# ETHERNET_PHY0.net
KiCad netlist of a schematic drawn in Altium Designer
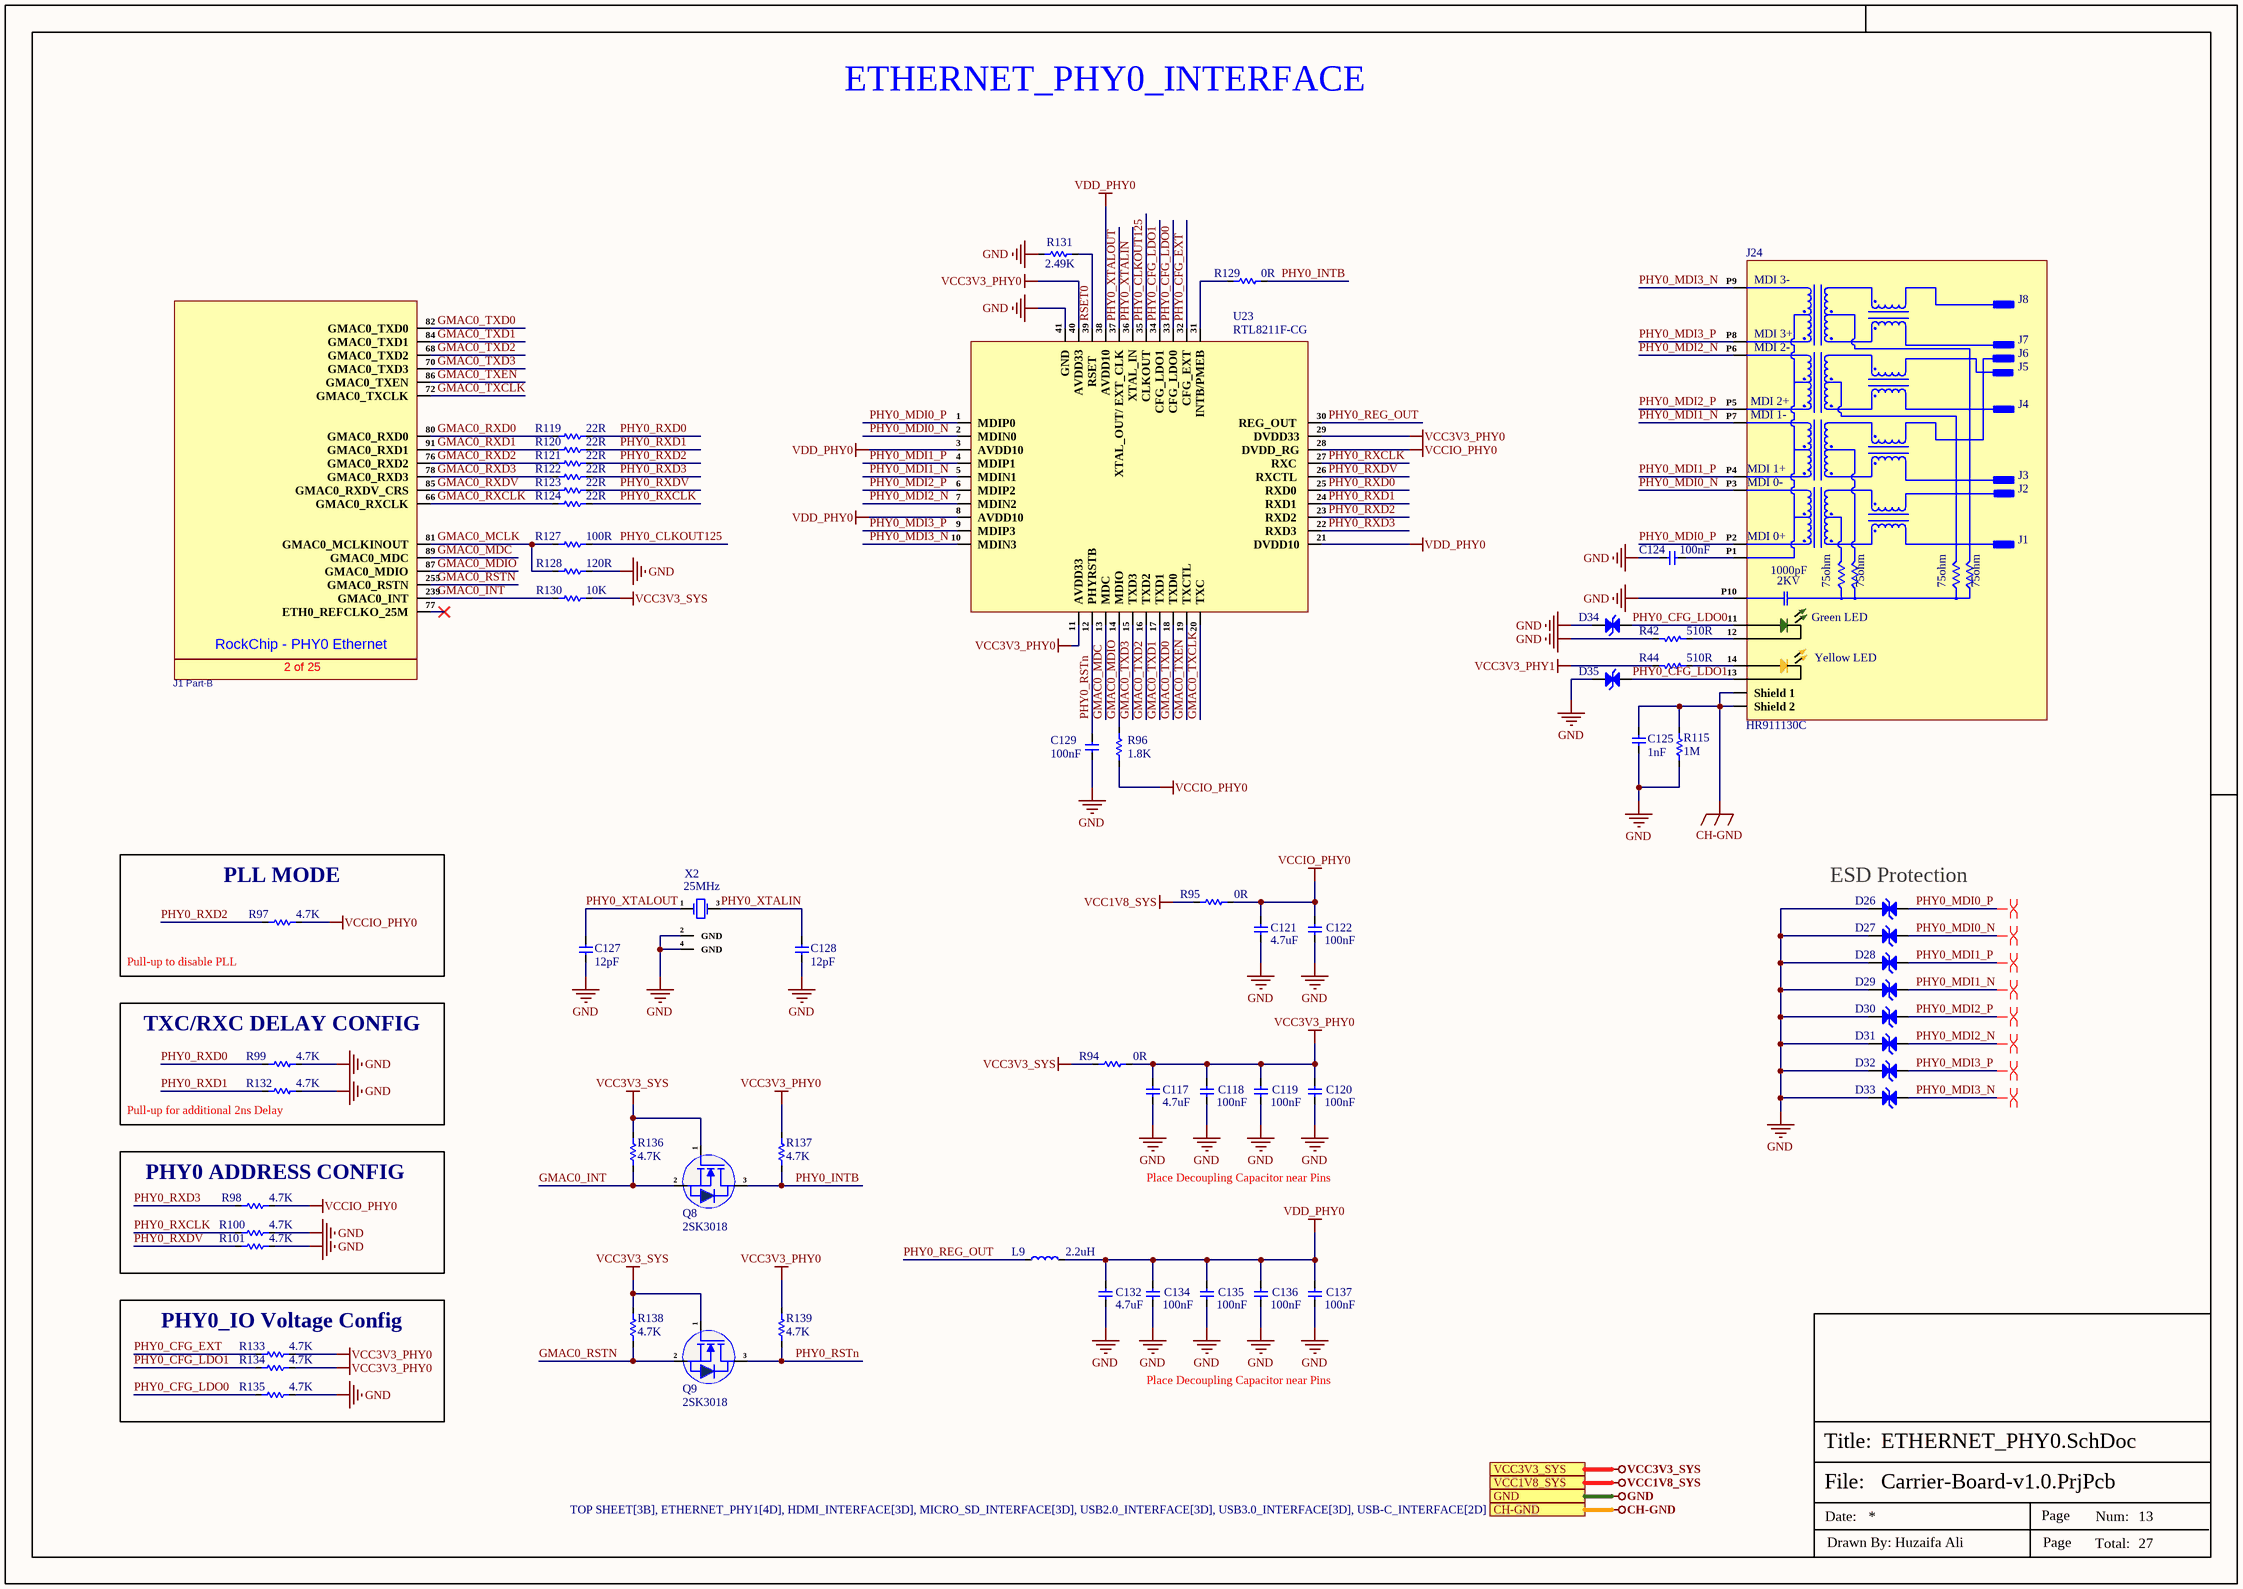
[diagram p0: ETHERNET_PHY0.SchDoc]

(export (version "E")
  (design (tool "Eeschema 10.0.6"))
  (components
    (comp (ref "C117")
      (value "4.7uF")
      (footprint "Cap-0402")
      (description "CAP CER 4.7UF 10V X5R 0402")
      (fields
        (field (name "MANUFACTURER") "Yageo")
        (field (name "MANUFACTURER PART NUMBER") "CC0402KRX5R6BB475")
      )
      (libsource (lib "eSpark Libraries") (part "CC0402KRX5R6BB475"))
    )
    (comp (ref "C118")
      (value "100nF")
      (footprint "Cap-0402")
      (description "CAP CER 0.1UF 16V X5R 0402")
      (fields
        (field (name "MANUFACTURER") "Yageo")
        (field (name "MANUFACTURER PART NUMBER") "CC0402KRX5R7BB104")
      )
      (libsource (lib "eSpark Libraries") (part "CC0402KRX5R7BB104"))
    )
    (comp (ref "C119")
      (value "100nF")
      (footprint "Cap-0402")
      (description "CAP CER 0.1UF 16V X5R 0402")
      (fields
        (field (name "MANUFACTURER") "Yageo")
        (field (name "MANUFACTURER PART NUMBER") "CC0402KRX5R7BB104")
      )
      (libsource (lib "eSpark Libraries") (part "CC0402KRX5R7BB104"))
    )
    (comp (ref "C120")
      (value "100nF")
      (footprint "Cap-0402")
      (description "CAP CER 0.1UF 16V X5R 0402")
      (fields
        (field (name "MANUFACTURER") "Yageo")
        (field (name "MANUFACTURER PART NUMBER") "CC0402KRX5R7BB104")
      )
      (libsource (lib "eSpark Libraries") (part "CC0402KRX5R7BB104"))
    )
    (comp (ref "C121")
      (value "4.7uF")
      (footprint "Cap-0402")
      (description "CAP CER 4.7UF 10V X5R 0402")
      (fields
        (field (name "MANUFACTURER") "Yageo")
        (field (name "MANUFACTURER PART NUMBER") "CC0402KRX5R6BB475")
      )
      (libsource (lib "eSpark Libraries") (part "CC0402KRX5R6BB475"))
    )
    (comp (ref "C122")
      (value "100nF")
      (footprint "Cap-0402")
      (description "CAP CER 0.1UF 16V X5R 0402")
      (fields
        (field (name "MANUFACTURER") "Yageo")
        (field (name "MANUFACTURER PART NUMBER") "CC0402KRX5R7BB104")
      )
      (libsource (lib "eSpark Libraries") (part "CC0402KRX5R7BB104"))
    )
    (comp (ref "C124")
      (value "100nF")
      (footprint "cap-0402")
      (description "CAP CER 0.1UF 50V X7R 0402")
      (fields
        (field (name "MANUFACTURER") "TDK")
        (field (name "MANUFACTURER PART NUMBER") "C1005X7R1H104KT000F")
      )
      (libsource (lib "eSpark Libraries") (part "C1005X7R1H104KT000F"))
    )
    (comp (ref "C125")
      (value "1nF")
      (footprint "Cap-1206")
      (description "CAP CER 1000PF 2KV X7R 1206")
      (fields
        (field (name "MANUFACTURER") "Yageo")
        (field (name "MANUFACTURER PART NUMBER") "CC1206KKX7RDBB102")
      )
      (libsource (lib "eSpark Libraries") (part "CC1206KKX7RDBB102"))
    )
    (comp (ref "C127")
      (value "12pF")
      (footprint "Cap-0402")
      (description "CAP CER 12PF 50V C0G/NP0 0402")
      (fields
        (field (name "MANUFACTURER") "Murata")
        (field (name "MANUFACTURER PART NUMBER") "GJM1555C1H120GB01D")
      )
      (libsource (lib "eSpark Libraries") (part "GJM1555C1H120GB01D"))
    )
    (comp (ref "C128")
      (value "12pF")
      (footprint "Cap-0402")
      (description "CAP CER 12PF 50V C0G/NP0 0402")
      (fields
        (field (name "MANUFACTURER") "Murata")
        (field (name "MANUFACTURER PART NUMBER") "GJM1555C1H120GB01D")
      )
      (libsource (lib "eSpark Libraries") (part "GJM1555C1H120GB01D"))
    )
    (comp (ref "C129")
      (value "100nF")
      (footprint "Cap-0402")
      (description "CAP CER 0.1UF 16V X5R 0402")
      (fields
        (field (name "MANUFACTURER") "Yageo")
        (field (name "MANUFACTURER PART NUMBER") "CC0402KRX5R7BB104")
      )
      (libsource (lib "eSpark Libraries") (part "CC0402KRX5R7BB104"))
    )
    (comp (ref "C132")
      (value "4.7uF")
      (footprint "Cap-0402")
      (description "CAP CER 4.7UF 10V X5R 0402")
      (fields
        (field (name "MANUFACTURER") "Yageo")
        (field (name "MANUFACTURER PART NUMBER") "CC0402KRX5R6BB475")
      )
      (libsource (lib "eSpark Libraries") (part "CC0402KRX5R6BB475"))
    )
    (comp (ref "C134")
      (value "100nF")
      (footprint "Cap-0402")
      (description "CAP CER 0.1UF 16V X5R 0402")
      (fields
        (field (name "MANUFACTURER") "Yageo")
        (field (name "MANUFACTURER PART NUMBER") "CC0402KRX5R7BB104")
      )
      (libsource (lib "eSpark Libraries") (part "CC0402KRX5R7BB104"))
    )
    (comp (ref "C135")
      (value "100nF")
      (footprint "Cap-0402")
      (description "CAP CER 0.1UF 16V X5R 0402")
      (fields
        (field (name "MANUFACTURER") "Yageo")
        (field (name "MANUFACTURER PART NUMBER") "CC0402KRX5R7BB104")
      )
      (libsource (lib "eSpark Libraries") (part "CC0402KRX5R7BB104"))
    )
    (comp (ref "C136")
      (value "100nF")
      (footprint "Cap-0402")
      (description "CAP CER 0.1UF 16V X5R 0402")
      (fields
        (field (name "MANUFACTURER") "Yageo")
        (field (name "MANUFACTURER PART NUMBER") "CC0402KRX5R7BB104")
      )
      (libsource (lib "eSpark Libraries") (part "CC0402KRX5R7BB104"))
    )
    (comp (ref "C137")
      (value "100nF")
      (footprint "Cap-0402")
      (description "CAP CER 0.1UF 16V X5R 0402")
      (fields
        (field (name "MANUFACTURER") "Yageo")
        (field (name "MANUFACTURER PART NUMBER") "CC0402KRX5R7BB104")
      )
      (libsource (lib "eSpark Libraries") (part "CC0402KRX5R7BB104"))
    )
    (comp (ref "D26")
      (value "ESD9X5VU")
      (footprint "DFN1006-2L_")
      (description "DFN1006-2 ESD Protection Devices ROHS")
      (fields (field (name "MANUFACTURER") "TECH PUBLIC") (field (name "LCSC PART NUMBER") "C2875160"))
      (libsource (lib "eSpark Libraries") (part "ESD9X5VU"))
    )
    (comp (ref "D27")
      (value "ESD9X5VU")
      (footprint "DFN1006-2L_")
      (description "DFN1006-2 ESD Protection Devices ROHS")
      (fields (field (name "MANUFACTURER") "TECH PUBLIC") (field (name "LCSC PART NUMBER") "C2875160"))
      (libsource (lib "eSpark Libraries") (part "ESD9X5VU"))
    )
    (comp (ref "D28")
      (value "ESD9X5VU")
      (footprint "DFN1006-2L_")
      (description "DFN1006-2 ESD Protection Devices ROHS")
      (fields (field (name "MANUFACTURER") "TECH PUBLIC") (field (name "LCSC PART NUMBER") "C2875160"))
      (libsource (lib "eSpark Libraries") (part "ESD9X5VU"))
    )
    (comp (ref "D29")
      (value "ESD9X5VU")
      (footprint "DFN1006-2L_")
      (description "DFN1006-2 ESD Protection Devices ROHS")
      (fields (field (name "MANUFACTURER") "TECH PUBLIC") (field (name "LCSC PART NUMBER") "C2875160"))
      (libsource (lib "eSpark Libraries") (part "ESD9X5VU"))
    )
    (comp (ref "D30")
      (value "ESD9X5VU")
      (footprint "DFN1006-2L_")
      (description "DFN1006-2 ESD Protection Devices ROHS")
      (fields (field (name "MANUFACTURER") "TECH PUBLIC") (field (name "LCSC PART NUMBER") "C2875160"))
      (libsource (lib "eSpark Libraries") (part "ESD9X5VU"))
    )
    (comp (ref "D31")
      (value "ESD9X5VU")
      (footprint "DFN1006-2L_")
      (description "DFN1006-2 ESD Protection Devices ROHS")
      (fields (field (name "MANUFACTURER") "TECH PUBLIC") (field (name "LCSC PART NUMBER") "C2875160"))
      (libsource (lib "eSpark Libraries") (part "ESD9X5VU"))
    )
    (comp (ref "D32")
      (value "ESD9X5VU")
      (footprint "DFN1006-2L_")
      (description "DFN1006-2 ESD Protection Devices ROHS")
      (fields (field (name "MANUFACTURER") "TECH PUBLIC") (field (name "LCSC PART NUMBER") "C2875160"))
      (libsource (lib "eSpark Libraries") (part "ESD9X5VU"))
    )
    (comp (ref "D33")
      (value "ESD9X5VU")
      (footprint "DFN1006-2L_")
      (description "DFN1006-2 ESD Protection Devices ROHS")
      (fields (field (name "MANUFACTURER") "TECH PUBLIC") (field (name "LCSC PART NUMBER") "C2875160"))
      (libsource (lib "eSpark Libraries") (part "ESD9X5VU"))
    )
    (comp (ref "D34")
      (value "ESD9X5VU")
      (footprint "DFN1006-2L_")
      (description "DFN1006-2 ESD Protection Devices ROHS")
      (fields (field (name "MANUFACTURER") "TECH PUBLIC") (field (name "LCSC PART NUMBER") "C2875160"))
      (libsource (lib "eSpark Libraries") (part "ESD9X5VU"))
    )
    (comp (ref "D35")
      (value "ESD9X5VU")
      (footprint "DFN1006-2L_")
      (description "DFN1006-2 ESD Protection Devices ROHS")
      (fields (field (name "MANUFACTURER") "TECH PUBLIC") (field (name "LCSC PART NUMBER") "C2875160"))
      (libsource (lib "eSpark Libraries") (part "ESD9X5VU"))
    )
    (comp (ref "J1 Part-")
      (value "AS0B826-S78B-7H")
      (footprint "AS0B826-S78B-7H")
      (description "SMD,P=0.5mm,Surface Mount，Right Angle")
      (fields (field (name "MANUFACTURER") "FOXCONN") (field (name "LCSC PART NUMBER") "C426232"))
      (libsource (lib "eSpark Libraries") (part "AS0B826-S78B-7H"))
    )
    (comp (ref "J24")
      (value "HR911130C")
      (footprint "HR911130C")
      (fields (field (name "MANUFACTURER") "HANRUN") (field (name "LCSC PART NUMBER") "C50933"))
      (libsource (lib "eSpark Libraries") (part "HR911130C"))
    )
    (comp (ref "L9")
      (value "2.2uH")
      (footprint "MAKK2016T2R2M_")
      (description "FIXED IND 2.2UH 1.5A 160MOHM SMD")
      (fields
        (field (name "MANUFACTURER") "Taiyo Yuden")
        (field (name "MANUFACTURER PART NUMBER") "MAKK2016T2R2M")
      )
      (libsource (lib "eSpark Libraries") (part "MAKK2016T2R2M"))
    )
    (comp (ref "Q8")
      (value "2SK3018")
      (footprint "SOT-23")
      (description "30V 100mA 200mW 8Ω@4V,10mA N Channel SOT-23 MOSFETs ROHS")
      (fields (field (name "MANUFACTURER") "KUU") (field (name "LCSC PART NUMBER") "C2944164"))
      (libsource (lib "eSpark Libraries") (part "2SK3018"))
    )
    (comp (ref "Q9")
      (value "2SK3018")
      (footprint "SOT-23")
      (description "30V 100mA 200mW 8Ω@4V,10mA N Channel SOT-23 MOSFETs ROHS")
      (fields (field (name "MANUFACTURER") "KUU") (field (name "LCSC PART NUMBER") "C2944164"))
      (libsource (lib "eSpark Libraries") (part "2SK3018"))
    )
    (comp (ref "R42")
      (value "510R")
      (footprint "Res-0402")
      (description "RES SMD 510 OHM 1% 1/16W 0402")
      (fields
        (field (name "MANUFACTURER") "Yageo")
        (field (name "MANUFACTURER PART NUMBER") "RT0402FRE07510RL")
      )
      (libsource (lib "eSpark Libraries") (part "RT0402FRE07510RL"))
    )
    (comp (ref "R44")
      (value "510R")
      (footprint "Res-0402")
      (description "RES SMD 510 OHM 1% 1/16W 0402")
      (fields
        (field (name "MANUFACTURER") "Yageo")
        (field (name "MANUFACTURER PART NUMBER") "RT0402FRE07510RL")
      )
      (libsource (lib "eSpark Libraries") (part "RT0402FRE07510RL"))
    )
    (comp (ref "R94")
      (value "0R")
      (footprint "Res-0603")
      (description "RES 0 OHM JUMPER 1/10W 0603")
      (fields
        (field (name "MANUFACTURER") "Yageo")
        (field (name "MANUFACTURER PART NUMBER") "RC0603JR-070RL")
      )
      (libsource (lib "eSpark Libraries") (part "RC0603JR-070RL"))
    )
    (comp (ref "R95")
      (value "0R")
      (footprint "Res-0603")
      (description "RES 0 OHM JUMPER 1/10W 0603")
      (fields
        (field (name "MANUFACTURER") "Yageo")
        (field (name "MANUFACTURER PART NUMBER") "RC0603JR-070RL")
      )
      (libsource (lib "eSpark Libraries") (part "RC0603JR-070RL"))
    )
    (comp (ref "R96")
      (value "1.8K")
      (footprint "Res-0402")
      (description "RES SMD 1.8K OHM 1% 1/5W 0402")
      (fields
        (field (name "MANUFACTURER") "Vishay Dale")
        (field (name "MANUFACTURER PART NUMBER") "RCS04021K80FKED")
      )
      (libsource (lib "eSpark Libraries") (part "RCS04021K80FKED"))
    )
    (comp (ref "R97")
      (value "4.7K")
      (footprint "Res-0402")
      (description "RES 4.7K OHM 1% 1/16W 0402")
      (fields
        (field (name "MANUFACTURER") "Yageo")
        (field (name "MANUFACTURER PART NUMBER") "RC0402FR-074K7L")
      )
      (libsource (lib "eSpark Libraries") (part "RC0402FR-074K7L"))
    )
    (comp (ref "R98")
      (value "4.7K")
      (footprint "Res-0402")
      (description "RES 4.7K OHM 1% 1/16W 0402")
      (fields
        (field (name "MANUFACTURER") "Yageo")
        (field (name "MANUFACTURER PART NUMBER") "RC0402FR-074K7L")
      )
      (libsource (lib "eSpark Libraries") (part "RC0402FR-074K7L"))
    )
    (comp (ref "R99")
      (value "4.7K")
      (footprint "Res-0402")
      (description "RES 4.7K OHM 1% 1/16W 0402")
      (fields
        (field (name "MANUFACTURER") "Yageo")
        (field (name "MANUFACTURER PART NUMBER") "RC0402FR-074K7L")
      )
      (libsource (lib "eSpark Libraries") (part "RC0402FR-074K7L"))
    )
    (comp (ref "R100")
      (value "4.7K")
      (footprint "Res-0402")
      (description "RES 4.7K OHM 1% 1/16W 0402")
      (fields
        (field (name "MANUFACTURER") "Yageo")
        (field (name "MANUFACTURER PART NUMBER") "RC0402FR-074K7L")
      )
      (libsource (lib "eSpark Libraries") (part "RC0402FR-074K7L"))
    )
    (comp (ref "R101")
      (value "4.7K")
      (footprint "Res-0402")
      (description "RES 4.7K OHM 1% 1/16W 0402")
      (fields
        (field (name "MANUFACTURER") "Yageo")
        (field (name "MANUFACTURER PART NUMBER") "RC0402FR-074K7L")
      )
      (libsource (lib "eSpark Libraries") (part "RC0402FR-074K7L"))
    )
    (comp (ref "R115")
      (value "1M")
      (footprint "Res-0402")
      (description "RES SMD 1M OHM 5% 1/16W 0402")
      (fields
        (field (name "MANUFACTURER") "Yageo")
        (field (name "MANUFACTURER PART NUMBER") "AF0402JR-071ML")
      )
      (libsource (lib "eSpark Libraries") (part "AF0402JR-071ML"))
    )
    (comp (ref "R119")
      (value "22R")
      (footprint "Res-0402")
      (description "RES 22 OHM 1% 1/16W 0402")
      (fields
        (field (name "MANUFACTURER") "Yageo")
        (field (name "MANUFACTURER PART NUMBER") "RC0402FR-0722RL")
      )
      (libsource (lib "eSpark Libraries") (part "RC0402FR-0722RL"))
    )
    (comp (ref "R120")
      (value "22R")
      (footprint "Res-0402")
      (description "RES 22 OHM 1% 1/16W 0402")
      (fields
        (field (name "MANUFACTURER") "Yageo")
        (field (name "MANUFACTURER PART NUMBER") "RC0402FR-0722RL")
      )
      (libsource (lib "eSpark Libraries") (part "RC0402FR-0722RL"))
    )
    (comp (ref "R121")
      (value "22R")
      (footprint "Res-0402")
      (description "RES 22 OHM 1% 1/16W 0402")
      (fields
        (field (name "MANUFACTURER") "Yageo")
        (field (name "MANUFACTURER PART NUMBER") "RC0402FR-0722RL")
      )
      (libsource (lib "eSpark Libraries") (part "RC0402FR-0722RL"))
    )
    (comp (ref "R122")
      (value "22R")
      (footprint "Res-0402")
      (description "RES 22 OHM 1% 1/16W 0402")
      (fields
        (field (name "MANUFACTURER") "Yageo")
        (field (name "MANUFACTURER PART NUMBER") "RC0402FR-0722RL")
      )
      (libsource (lib "eSpark Libraries") (part "RC0402FR-0722RL"))
    )
    (comp (ref "R123")
      (value "22R")
      (footprint "Res-0402")
      (description "RES 22 OHM 1% 1/16W 0402")
      (fields
        (field (name "MANUFACTURER") "Yageo")
        (field (name "MANUFACTURER PART NUMBER") "RC0402FR-0722RL")
      )
      (libsource (lib "eSpark Libraries") (part "RC0402FR-0722RL"))
    )
    (comp (ref "R124")
      (value "22R")
      (footprint "Res-0402")
      (description "RES 22 OHM 1% 1/16W 0402")
      (fields
        (field (name "MANUFACTURER") "Yageo")
        (field (name "MANUFACTURER PART NUMBER") "RC0402FR-0722RL")
      )
      (libsource (lib "eSpark Libraries") (part "RC0402FR-0722RL"))
    )
    (comp (ref "R127")
      (value "100R")
      (footprint "Res-0402")
      (description "RES 100 OHM 1% 1/16W 0402")
      (fields
        (field (name "MANUFACTURER") "Yageo")
        (field (name "MANUFACTURER PART NUMBER") "RC0402FR-07100RL")
      )
      (libsource (lib "eSpark Libraries") (part "RC0402FR-07100RL"))
    )
    (comp (ref "R128")
      (value "120R")
      (footprint "Res-0402")
      (description "RES 120 OHM 1% 1/16W 0402")
      (fields
        (field (name "MANUFACTURER") "Yageo")
        (field (name "MANUFACTURER PART NUMBER") "RC0402FR-07120RL")
      )
      (libsource (lib "eSpark Libraries") (part "RC0402FR-07120RL"))
    )
    (comp (ref "R129")
      (value "0R")
      (footprint "Res-0402")
      (description "RES 0 OHM JUMPER 1/16W 0402")
      (fields
        (field (name "MANUFACTURER") "Yageo")
        (field (name "MANUFACTURER PART NUMBER") "RC0402FR-070RL")
      )
      (libsource (lib "eSpark Libraries") (part "RC0402FR-070RL"))
    )
    (comp (ref "R130")
      (value "10K")
      (footprint "Res-0402")
      (description "RES 10K OHM 1% 1/16W 0402")
      (fields
        (field (name "MANUFACTURER") "Yageo")
        (field (name "MANUFACTURER PART NUMBER") "RC0402FR-0710KL")
      )
      (libsource (lib "eSpark Libraries") (part "RC0402FR-0710KL"))
    )
    (comp (ref "R131")
      (value "2.49K")
      (footprint "Res-0402")
      (description "RES 2.49K OHM 1% 1/16W 0402")
      (fields
        (field (name "MANUFACTURER") "Yageo")
        (field (name "MANUFACTURER PART NUMBER") "RC0402FR-072K49L")
      )
      (libsource (lib "eSpark Libraries") (part "RC0402FR-072K49L"))
    )
    (comp (ref "R132")
      (value "4.7K")
      (footprint "Res-0402")
      (description "RES 4.7K OHM 1% 1/16W 0402")
      (fields
        (field (name "MANUFACTURER") "Yageo")
        (field (name "MANUFACTURER PART NUMBER") "RC0402FR-074K7L")
      )
      (libsource (lib "eSpark Libraries") (part "RC0402FR-074K7L"))
    )
    (comp (ref "R133")
      (value "4.7K")
      (footprint "Res-0402")
      (description "RES 4.7K OHM 1% 1/16W 0402")
      (fields
        (field (name "MANUFACTURER") "Yageo")
        (field (name "MANUFACTURER PART NUMBER") "RC0402FR-074K7L")
      )
      (libsource (lib "eSpark Libraries") (part "RC0402FR-074K7L"))
    )
    (comp (ref "R134")
      (value "4.7K")
      (footprint "Res-0402")
      (description "RES 4.7K OHM 1% 1/16W 0402")
      (fields
        (field (name "MANUFACTURER") "Yageo")
        (field (name "MANUFACTURER PART NUMBER") "RC0402FR-074K7L")
      )
      (libsource (lib "eSpark Libraries") (part "RC0402FR-074K7L"))
    )
    (comp (ref "R135")
      (value "4.7K")
      (footprint "Res-0402")
      (description "RES 4.7K OHM 1% 1/16W 0402")
      (fields
        (field (name "MANUFACTURER") "Yageo")
        (field (name "MANUFACTURER PART NUMBER") "RC0402FR-074K7L")
      )
      (libsource (lib "eSpark Libraries") (part "RC0402FR-074K7L"))
    )
    (comp (ref "R136")
      (value "4.7K")
      (footprint "Res-0402")
      (description "RES 4.7K OHM 1% 1/16W 0402")
      (fields
        (field (name "MANUFACTURER") "Yageo")
        (field (name "MANUFACTURER PART NUMBER") "RC0402FR-074K7L")
      )
      (libsource (lib "eSpark Libraries") (part "RC0402FR-074K7L"))
    )
    (comp (ref "R137")
      (value "4.7K")
      (footprint "Res-0402")
      (description "RES 4.7K OHM 1% 1/16W 0402")
      (fields
        (field (name "MANUFACTURER") "Yageo")
        (field (name "MANUFACTURER PART NUMBER") "RC0402FR-074K7L")
      )
      (libsource (lib "eSpark Libraries") (part "RC0402FR-074K7L"))
    )
    (comp (ref "R138")
      (value "4.7K")
      (footprint "Res-0402")
      (description "RES 4.7K OHM 1% 1/16W 0402")
      (fields
        (field (name "MANUFACTURER") "Yageo")
        (field (name "MANUFACTURER PART NUMBER") "RC0402FR-074K7L")
      )
      (libsource (lib "eSpark Libraries") (part "RC0402FR-074K7L"))
    )
    (comp (ref "R139")
      (value "4.7K")
      (footprint "Res-0402")
      (description "RES 4.7K OHM 1% 1/16W 0402")
      (fields
        (field (name "MANUFACTURER") "Yageo")
        (field (name "MANUFACTURER PART NUMBER") "RC0402FR-074K7L")
      )
      (libsource (lib "eSpark Libraries") (part "RC0402FR-074K7L"))
    )
    (comp (ref "U23")
      (value "RTL8211F-CG")
      (footprint "WQFN-40-EP(5x5)")
      (description "WQFN-40-EP(5x5) Ethernet ICs ROHS")
      (fields (field (name "MANUFACTURER") "Realtek Semicon") (field (name "LCSC PART NUMBER") "C187932"))
      (libsource (lib "eSpark Libraries") (part "RTL8211F-CG"))
    )
    (comp (ref "X2")
      (value "25MHz")
      (footprint "Q22FA12800090")
      (description "CRYSTAL 25.0000MHZ 12PF SMD")
      (fields
        (field (name "MANUFACTURER") "Seiko Epson")
        (field (name "MANUFACTURER PART NUMBER") "Q22FA12800090")
      )
      (libsource (lib "eSpark Libraries") (part "Q22FA12800090"))
    )
  )
  (nets
    (net (code "1") (name "/GMAC0_INT") (class "Default")
      (node (ref "J1 Part-") (pin "239") (pinfunction "GMAC0_INT_239") (pintype "passive"))
      (node (ref "Q8") (pin "2") (pinfunction "S_2") (pintype "passive"))
      (node (ref "R130") (pin "2") (pinfunction "2_2") (pintype "passive"))
      (node (ref "R136") (pin "1") (pinfunction "1_1") (pintype "passive"))
    )
    (net (code "2") (name "/GMAC0_MCLK") (class "Default")
      (node (ref "J1 Part-") (pin "81") (pinfunction "GMAC0_MCLKINOUT_81") (pintype "passive"))
      (node (ref "R127") (pin "1") (pinfunction "1_1") (pintype "passive"))
      (node (ref "R128") (pin "2") (pinfunction "2_2") (pintype "passive"))
    )
    (net (code "3") (name "/GMAC0_MDC") (class "Default")
      (node (ref "J1 Part-") (pin "89") (pinfunction "GMAC0_MDC_89") (pintype "passive"))
      (node (ref "U23") (pin "13") (pinfunction "MDC_13") (pintype "passive"))
    )
    (net (code "4") (name "/GMAC0_MDIO") (class "Default")
      (node (ref "J1 Part-") (pin "87") (pinfunction "GMAC0_MDIO_87") (pintype "passive"))
      (node (ref "R96") (pin "1") (pinfunction "1_1") (pintype "passive"))
      (node (ref "U23") (pin "14") (pinfunction "MDIO_14") (pintype "passive"))
    )
    (net (code "5") (name "/GMAC0_RSTN") (class "Default")
      (node (ref "J1 Part-") (pin "255") (pinfunction "GMAC0_RSTN_255") (pintype "passive"))
      (node (ref "Q9") (pin "2") (pinfunction "S_2") (pintype "passive"))
      (node (ref "R138") (pin "1") (pinfunction "1_1") (pintype "passive"))
    )
    (net (code "6") (name "/GMAC0_RXCLK") (class "Default")
      (node (ref "J1 Part-") (pin "66") (pinfunction "GMAC0_RXCLK_66") (pintype "passive"))
      (node (ref "R124") (pin "1") (pinfunction "1_1") (pintype "passive"))
    )
    (net (code "7") (name "/GMAC0_RXD0") (class "Default")
      (node (ref "J1 Part-") (pin "80") (pinfunction "GMAC0_RXD0_80") (pintype "passive"))
      (node (ref "R119") (pin "1") (pinfunction "1_1") (pintype "passive"))
    )
    (net (code "8") (name "/GMAC0_RXD1") (class "Default")
      (node (ref "J1 Part-") (pin "91") (pinfunction "GMAC0_RXD1_91") (pintype "passive"))
      (node (ref "R120") (pin "1") (pinfunction "1_1") (pintype "passive"))
    )
    (net (code "9") (name "/GMAC0_RXD2") (class "Default")
      (node (ref "J1 Part-") (pin "76") (pinfunction "GMAC0_RXD2_76") (pintype "passive"))
      (node (ref "R121") (pin "1") (pinfunction "1_1") (pintype "passive"))
    )
    (net (code "10") (name "/GMAC0_RXD3") (class "Default")
      (node (ref "J1 Part-") (pin "78") (pinfunction "GMAC0_RXD3_78") (pintype "passive"))
      (node (ref "R122") (pin "1") (pinfunction "1_1") (pintype "passive"))
    )
    (net (code "11") (name "/GMAC0_RXDV") (class "Default")
      (node (ref "J1 Part-") (pin "85") (pinfunction "GMAC0_RXDV_CRS_85") (pintype "passive"))
      (node (ref "R123") (pin "1") (pinfunction "1_1") (pintype "passive"))
    )
    (net (code "12") (name "/GMAC0_TXCLK") (class "Default")
      (node (ref "J1 Part-") (pin "72") (pinfunction "GMAC0_TXCLK_72") (pintype "passive"))
      (node (ref "U23") (pin "20") (pinfunction "TXC_20") (pintype "passive"))
    )
    (net (code "13") (name "/GMAC0_TXD0") (class "Default")
      (node (ref "J1 Part-") (pin "82") (pinfunction "GMAC0_TXD0_82") (pintype "passive"))
      (node (ref "U23") (pin "18") (pinfunction "TXD0_18") (pintype "passive"))
    )
    (net (code "14") (name "/GMAC0_TXD1") (class "Default")
      (node (ref "J1 Part-") (pin "84") (pinfunction "GMAC0_TXD1_84") (pintype "passive"))
      (node (ref "U23") (pin "17") (pinfunction "TXD1_17") (pintype "passive"))
    )
    (net (code "15") (name "/GMAC0_TXD2") (class "Default")
      (node (ref "J1 Part-") (pin "68") (pinfunction "GMAC0_TXD2_68") (pintype "passive"))
      (node (ref "U23") (pin "16") (pinfunction "TXD2_16") (pintype "passive"))
    )
    (net (code "16") (name "/GMAC0_TXD3") (class "Default")
      (node (ref "J1 Part-") (pin "70") (pinfunction "GMAC0_TXD3_70") (pintype "passive"))
      (node (ref "U23") (pin "15") (pinfunction "TXD3_15") (pintype "passive"))
    )
    (net (code "17") (name "/GMAC0_TXEN") (class "Default")
      (node (ref "J1 Part-") (pin "86") (pinfunction "GMAC0_TXEN_86") (pintype "passive"))
      (node (ref "U23") (pin "19") (pinfunction "TXCTL_19") (pintype "passive"))
    )
    (net (code "18") (name "/PHY0_CFG_EXT") (class "Default")
      (node (ref "R133") (pin "1") (pinfunction "1_1") (pintype "passive"))
      (node (ref "U23") (pin "32") (pinfunction "CFG_EXT_32") (pintype "passive"))
    )
    (net (code "19") (name "/PHY0_CFG_LDO0") (class "Default")
      (node (ref "D34") (pin "2") (pinfunction "A_2") (pintype "passive"))
      (node (ref "J24") (pin "11") (pintype "passive"))
      (node (ref "R135") (pin "1") (pinfunction "1_1") (pintype "passive"))
      (node (ref "U23") (pin "33") (pinfunction "CFG_LDO0_33") (pintype "passive"))
    )
    (net (code "20") (name "/PHY0_CFG_LDO1") (class "Default")
      (node (ref "D35") (pin "2") (pinfunction "A_2") (pintype "passive"))
      (node (ref "J24") (pin "13") (pintype "passive"))
      (node (ref "R134") (pin "1") (pinfunction "1_1") (pintype "passive"))
      (node (ref "U23") (pin "34") (pinfunction "CFG_LDO1_34") (pintype "passive"))
    )
    (net (code "21") (name "/PHY0_CLKOUT125") (class "Default")
      (node (ref "R127") (pin "2") (pinfunction "2_2") (pintype "passive"))
      (node (ref "U23") (pin "35") (pinfunction "CLKOUT_35") (pintype "passive"))
    )
    (net (code "22") (name "/PHY0_INTB") (class "Default")
      (node (ref "Q8") (pin "3") (pinfunction "D_3") (pintype "passive"))
      (node (ref "R129") (pin "2") (pinfunction "2_2") (pintype "passive"))
      (node (ref "R137") (pin "1") (pinfunction "1_1") (pintype "passive"))
    )
    (net (code "23") (name "/PHY0_MDI0_N") (class "Default")
      (node (ref "D27") (pin "2") (pinfunction "A_2") (pintype "passive"))
      (node (ref "J24") (pin "P3") (pinfunction "P4_P3") (pintype "passive"))
      (node (ref "U23") (pin "2") (pinfunction "MDIN0_2") (pintype "passive"))
    )
    (net (code "24") (name "/PHY0_MDI0_P") (class "Default")
      (node (ref "D26") (pin "2") (pinfunction "A_2") (pintype "passive"))
      (node (ref "J24") (pin "P2") (pinfunction "P2_P2") (pintype "passive"))
      (node (ref "U23") (pin "1") (pinfunction "MDIP0_1") (pintype "passive"))
    )
    (net (code "25") (name "/PHY0_MDI1_N") (class "Default")
      (node (ref "D29") (pin "2") (pinfunction "A_2") (pintype "passive"))
      (node (ref "J24") (pin "P7") (pinfunction "P7_P7") (pintype "passive"))
      (node (ref "U23") (pin "5") (pinfunction "MDIN1_5") (pintype "passive"))
    )
    (net (code "26") (name "/PHY0_MDI1_P") (class "Default")
      (node (ref "D28") (pin "2") (pinfunction "A_2") (pintype "passive"))
      (node (ref "J24") (pin "P4") (pinfunction "P4_P4") (pintype "passive"))
      (node (ref "U23") (pin "4") (pinfunction "MDIP1_4") (pintype "passive"))
    )
    (net (code "27") (name "/PHY0_MDI2_N") (class "Default")
      (node (ref "D31") (pin "2") (pinfunction "A_2") (pintype "passive"))
      (node (ref "J24") (pin "P6") (pinfunction "P6_P6") (pintype "passive"))
      (node (ref "U23") (pin "7") (pinfunction "MDIN2_7") (pintype "passive"))
    )
    (net (code "28") (name "/PHY0_MDI2_P") (class "Default")
      (node (ref "D30") (pin "2") (pinfunction "A_2") (pintype "passive"))
      (node (ref "J24") (pin "P5") (pinfunction "P5_P5") (pintype "passive"))
      (node (ref "U23") (pin "6") (pinfunction "MDIP2_6") (pintype "passive"))
    )
    (net (code "29") (name "/PHY0_MDI3_N") (class "Default")
      (node (ref "D33") (pin "2") (pinfunction "A_2") (pintype "passive"))
      (node (ref "J24") (pin "P9") (pinfunction "P9_P9") (pintype "passive"))
      (node (ref "U23") (pin "10") (pinfunction "MDIN3_10") (pintype "passive"))
    )
    (net (code "30") (name "/PHY0_MDI3_P") (class "Default")
      (node (ref "D32") (pin "2") (pinfunction "A_2") (pintype "passive"))
      (node (ref "J24") (pin "P8") (pinfunction "P8_P8") (pintype "passive"))
      (node (ref "U23") (pin "9") (pinfunction "MDIP3_9") (pintype "passive"))
    )
    (net (code "31") (name "/PHY0_REG_OUT") (class "Default")
      (node (ref "L9") (pin "1") (pinfunction "1_1") (pintype "passive"))
      (node (ref "U23") (pin "30") (pinfunction "REG_OUT_30") (pintype "passive"))
    )
    (net (code "32") (name "/PHY0_RSTn") (class "Default")
      (node (ref "C129") (pin "2") (pinfunction "2_2") (pintype "passive"))
      (node (ref "Q9") (pin "3") (pinfunction "D_3") (pintype "passive"))
      (node (ref "R139") (pin "1") (pinfunction "1_1") (pintype "passive"))
      (node (ref "U23") (pin "12") (pinfunction "PHYRSTB_12") (pintype "passive"))
    )
    (net (code "33") (name "/PHY0_RXCLK") (class "Default")
      (node (ref "R100") (pin "1") (pinfunction "1_1") (pintype "passive"))
      (node (ref "R124") (pin "2") (pinfunction "2_2") (pintype "passive"))
      (node (ref "U23") (pin "27") (pinfunction "RXC_27") (pintype "passive"))
    )
    (net (code "34") (name "/PHY0_RXD0") (class "Default")
      (node (ref "R119") (pin "2") (pinfunction "2_2") (pintype "passive"))
      (node (ref "R99") (pin "1") (pinfunction "1_1") (pintype "passive"))
      (node (ref "U23") (pin "25") (pinfunction "RXD0_25") (pintype "passive"))
    )
    (net (code "35") (name "/PHY0_RXD1") (class "Default")
      (node (ref "R120") (pin "2") (pinfunction "2_2") (pintype "passive"))
      (node (ref "R132") (pin "1") (pinfunction "1_1") (pintype "passive"))
      (node (ref "U23") (pin "24") (pinfunction "RXD1_24") (pintype "passive"))
    )
    (net (code "36") (name "/PHY0_RXD2") (class "Default")
      (node (ref "R121") (pin "2") (pinfunction "2_2") (pintype "passive"))
      (node (ref "R97") (pin "1") (pinfunction "1_1") (pintype "passive"))
      (node (ref "U23") (pin "23") (pinfunction "RXD2_23") (pintype "passive"))
    )
    (net (code "37") (name "/PHY0_RXD3") (class "Default")
      (node (ref "R122") (pin "2") (pinfunction "2_2") (pintype "passive"))
      (node (ref "R98") (pin "1") (pinfunction "1_1") (pintype "passive"))
      (node (ref "U23") (pin "22") (pinfunction "RXD3_22") (pintype "passive"))
    )
    (net (code "38") (name "/PHY0_RXDV") (class "Default")
      (node (ref "R101") (pin "1") (pinfunction "1_1") (pintype "passive"))
      (node (ref "R123") (pin "2") (pinfunction "2_2") (pintype "passive"))
      (node (ref "U23") (pin "26") (pinfunction "RXCTL_26") (pintype "passive"))
    )
    (net (code "39") (name "/PHY0_XTALIN") (class "Default")
      (node (ref "C128") (pin "2") (pinfunction "2_2") (pintype "passive"))
      (node (ref "U23") (pin "36") (pinfunction "XTAL_IN_36") (pintype "passive"))
      (node (ref "X2") (pin "3") (pinfunction "OSC2_3") (pintype "passive"))
    )
    (net (code "40") (name "/PHY0_XTALOUT") (class "Default")
      (node (ref "C127") (pin "2") (pinfunction "2_2") (pintype "passive"))
      (node (ref "U23") (pin "37") (pinfunction "XTAL_OUT/_EXT_CLK_37") (pintype "passive"))
      (node (ref "X2") (pin "1") (pinfunction "OSC1_1") (pintype "passive"))
    )
    (net (code "41") (name "/RSET0") (class "Default")
      (node (ref "R131") (pin "2") (pinfunction "2_2") (pintype "passive"))
      (node (ref "U23") (pin "39") (pinfunction "RSET_39") (pintype "passive"))
    )
    (net (code "42") (name "CH-GND") (class "Default")
      (node (ref "C125") (pin "2") (pinfunction "2_2") (pintype "passive"))
      (node (ref "J24") (pin "SH1") (pinfunction "Shield_1_SH1") (pintype "passive"))
      (node (ref "J24") (pin "SH2") (pinfunction "Shield_2_SH2") (pintype "passive"))
      (node (ref "R115") (pin "2") (pinfunction "2_2") (pintype "passive"))
    )
    (net (code "43") (name "GND") (class "Default")
      (node (ref "C117") (pin "1") (pinfunction "1_1") (pintype "passive"))
      (node (ref "C118") (pin "1") (pinfunction "1_1") (pintype "passive"))
      (node (ref "C119") (pin "1") (pinfunction "1_1") (pintype "passive"))
      (node (ref "C120") (pin "1") (pinfunction "1_1") (pintype "passive"))
      (node (ref "C121") (pin "1") (pinfunction "1_1") (pintype "passive"))
      (node (ref "C122") (pin "1") (pinfunction "1_1") (pintype "passive"))
      (node (ref "C124") (pin "1") (pinfunction "1_1") (pintype "passive"))
      (node (ref "C125") (pin "1") (pinfunction "1_1") (pintype "passive"))
      (node (ref "C127") (pin "1") (pinfunction "1_1") (pintype "passive"))
      (node (ref "C128") (pin "1") (pinfunction "1_1") (pintype "passive"))
      (node (ref "C129") (pin "1") (pinfunction "1_1") (pintype "passive"))
      (node (ref "C132") (pin "1") (pinfunction "1_1") (pintype "passive"))
      (node (ref "C134") (pin "1") (pinfunction "1_1") (pintype "passive"))
      (node (ref "C135") (pin "1") (pinfunction "1_1") (pintype "passive"))
      (node (ref "C136") (pin "1") (pinfunction "1_1") (pintype "passive"))
      (node (ref "C137") (pin "1") (pinfunction "1_1") (pintype "passive"))
      (node (ref "D26") (pin "1") (pinfunction "A_1") (pintype "passive"))
      (node (ref "D27") (pin "1") (pinfunction "A_1") (pintype "passive"))
      (node (ref "D28") (pin "1") (pinfunction "A_1") (pintype "passive"))
      (node (ref "D29") (pin "1") (pinfunction "A_1") (pintype "passive"))
      (node (ref "D30") (pin "1") (pinfunction "A_1") (pintype "passive"))
      (node (ref "D31") (pin "1") (pinfunction "A_1") (pintype "passive"))
      (node (ref "D32") (pin "1") (pinfunction "A_1") (pintype "passive"))
      (node (ref "D33") (pin "1") (pinfunction "A_1") (pintype "passive"))
      (node (ref "D34") (pin "1") (pinfunction "A_1") (pintype "passive"))
      (node (ref "D35") (pin "1") (pinfunction "A_1") (pintype "passive"))
      (node (ref "J24") (pin "P10") (pinfunction "P10_P10") (pintype "power_in"))
      (node (ref "R100") (pin "2") (pinfunction "2_2") (pintype "passive"))
      (node (ref "R101") (pin "2") (pinfunction "2_2") (pintype "passive"))
      (node (ref "R115") (pin "1") (pinfunction "1_1") (pintype "passive"))
      (node (ref "R128") (pin "1") (pinfunction "1_1") (pintype "passive"))
      (node (ref "R131") (pin "1") (pinfunction "1_1") (pintype "passive"))
      (node (ref "R132") (pin "2") (pinfunction "2_2") (pintype "passive"))
      (node (ref "R135") (pin "2") (pinfunction "2_2") (pintype "passive"))
      (node (ref "R42") (pin "2") (pinfunction "2_2") (pintype "passive"))
      (node (ref "R99") (pin "2") (pinfunction "2_2") (pintype "passive"))
      (node (ref "U23") (pin "41") (pinfunction "GND_41") (pintype "passive"))
      (node (ref "X2") (pin "2") (pinfunction "GND_2") (pintype "passive"))
      (node (ref "X2") (pin "4") (pinfunction "GND_4") (pintype "passive"))
    )
    (net (code "44") (name "Net-(C124-Pad2)") (class "Default")
      (node (ref "C124") (pin "2") (pinfunction "2_2") (pintype "passive"))
      (node (ref "J24") (pin "P1") (pinfunction "P1_P1") (pintype "passive"))
    )
    (net (code "45") (name "Net-(J24-Pad12)") (class "Default")
      (node (ref "J24") (pin "12") (pintype "passive"))
      (node (ref "R42") (pin "1") (pinfunction "1_1") (pintype "passive"))
    )
    (net (code "46") (name "Net-(J24-Pad14)") (class "Default")
      (node (ref "J24") (pin "14") (pintype "passive"))
      (node (ref "R44") (pin "2") (pinfunction "2_2") (pintype "passive"))
    )
    (net (code "47") (name "Net-(U23-INTB{slash}PMEB)") (class "Default")
      (node (ref "R129") (pin "1") (pinfunction "1_1") (pintype "passive"))
      (node (ref "U23") (pin "31") (pinfunction "INTB/PMEB_31") (pintype "passive"))
    )
    (net (code "48") (name "VCC1V8_SYS") (class "Default")
      (node (ref "R95") (pin "1") (pinfunction "1_1") (pintype "passive"))
    )
    (net (code "49") (name "VCC3V3_PHY0") (class "Default")
      (node (ref "C117") (pin "2") (pinfunction "2_2") (pintype "passive"))
      (node (ref "C118") (pin "2") (pinfunction "2_2") (pintype "passive"))
      (node (ref "C119") (pin "2") (pinfunction "2_2") (pintype "passive"))
      (node (ref "C120") (pin "2") (pinfunction "2_2") (pintype "passive"))
      (node (ref "R133") (pin "2") (pinfunction "2_2") (pintype "passive"))
      (node (ref "R134") (pin "2") (pinfunction "2_2") (pintype "passive"))
      (node (ref "R137") (pin "2") (pinfunction "2_2") (pintype "passive"))
      (node (ref "R139") (pin "2") (pinfunction "2_2") (pintype "passive"))
      (node (ref "R94") (pin "2") (pinfunction "2_2") (pintype "passive"))
      (node (ref "U23") (pin "11") (pinfunction "AVDD33_11") (pintype "passive"))
      (node (ref "U23") (pin "29") (pinfunction "DVDD33_29") (pintype "passive"))
      (node (ref "U23") (pin "40") (pinfunction "AVDD33_40") (pintype "passive"))
    )
    (net (code "50") (name "VCC3V3_PHY1") (class "Default")
      (node (ref "R44") (pin "1") (pinfunction "1_1") (pintype "passive"))
    )
    (net (code "51") (name "VCC3V3_SYS") (class "Default")
      (node (ref "Q8") (pin "1") (pinfunction "G_1") (pintype "passive"))
      (node (ref "Q9") (pin "1") (pinfunction "G_1") (pintype "passive"))
      (node (ref "R130") (pin "1") (pinfunction "1_1") (pintype "passive"))
      (node (ref "R136") (pin "2") (pinfunction "2_2") (pintype "passive"))
      (node (ref "R138") (pin "2") (pinfunction "2_2") (pintype "passive"))
      (node (ref "R94") (pin "1") (pinfunction "1_1") (pintype "passive"))
    )
    (net (code "52") (name "VCCIO_PHY0") (class "Default")
      (node (ref "C121") (pin "2") (pinfunction "2_2") (pintype "passive"))
      (node (ref "C122") (pin "2") (pinfunction "2_2") (pintype "passive"))
      (node (ref "R95") (pin "2") (pinfunction "2_2") (pintype "passive"))
      (node (ref "R96") (pin "2") (pinfunction "2_2") (pintype "passive"))
      (node (ref "R97") (pin "2") (pinfunction "2_2") (pintype "passive"))
      (node (ref "R98") (pin "2") (pinfunction "2_2") (pintype "passive"))
      (node (ref "U23") (pin "28") (pinfunction "DVDD_RG_28") (pintype "passive"))
    )
    (net (code "53") (name "VDD_PHY0") (class "Default")
      (node (ref "C132") (pin "2") (pinfunction "2_2") (pintype "passive"))
      (node (ref "C134") (pin "2") (pinfunction "2_2") (pintype "passive"))
      (node (ref "C135") (pin "2") (pinfunction "2_2") (pintype "passive"))
      (node (ref "C136") (pin "2") (pinfunction "2_2") (pintype "passive"))
      (node (ref "C137") (pin "2") (pinfunction "2_2") (pintype "passive"))
      (node (ref "L9") (pin "2") (pinfunction "2_2") (pintype "passive"))
      (node (ref "U23") (pin "21") (pinfunction "DVDD10_21") (pintype "passive"))
      (node (ref "U23") (pin "3") (pinfunction "AVDD10_3") (pintype "passive"))
      (node (ref "U23") (pin "38") (pinfunction "AVDD10_38") (pintype "passive"))
      (node (ref "U23") (pin "8") (pinfunction "AVDD10_8") (pintype "passive"))
    )
    (net (code "54") (name "unconnected-(J1 Part-B-ETH0_REFCLKO_25M-Pad77)") (class "Default")
      (node (ref "J1 Part-") (pin "77") (pinfunction "ETH0_REFCLKO_25M_77") (pintype "passive+no_connect"))
    )
  )
)
